# tx.net
KiCad netlist of a schematic drawn in EAGLE
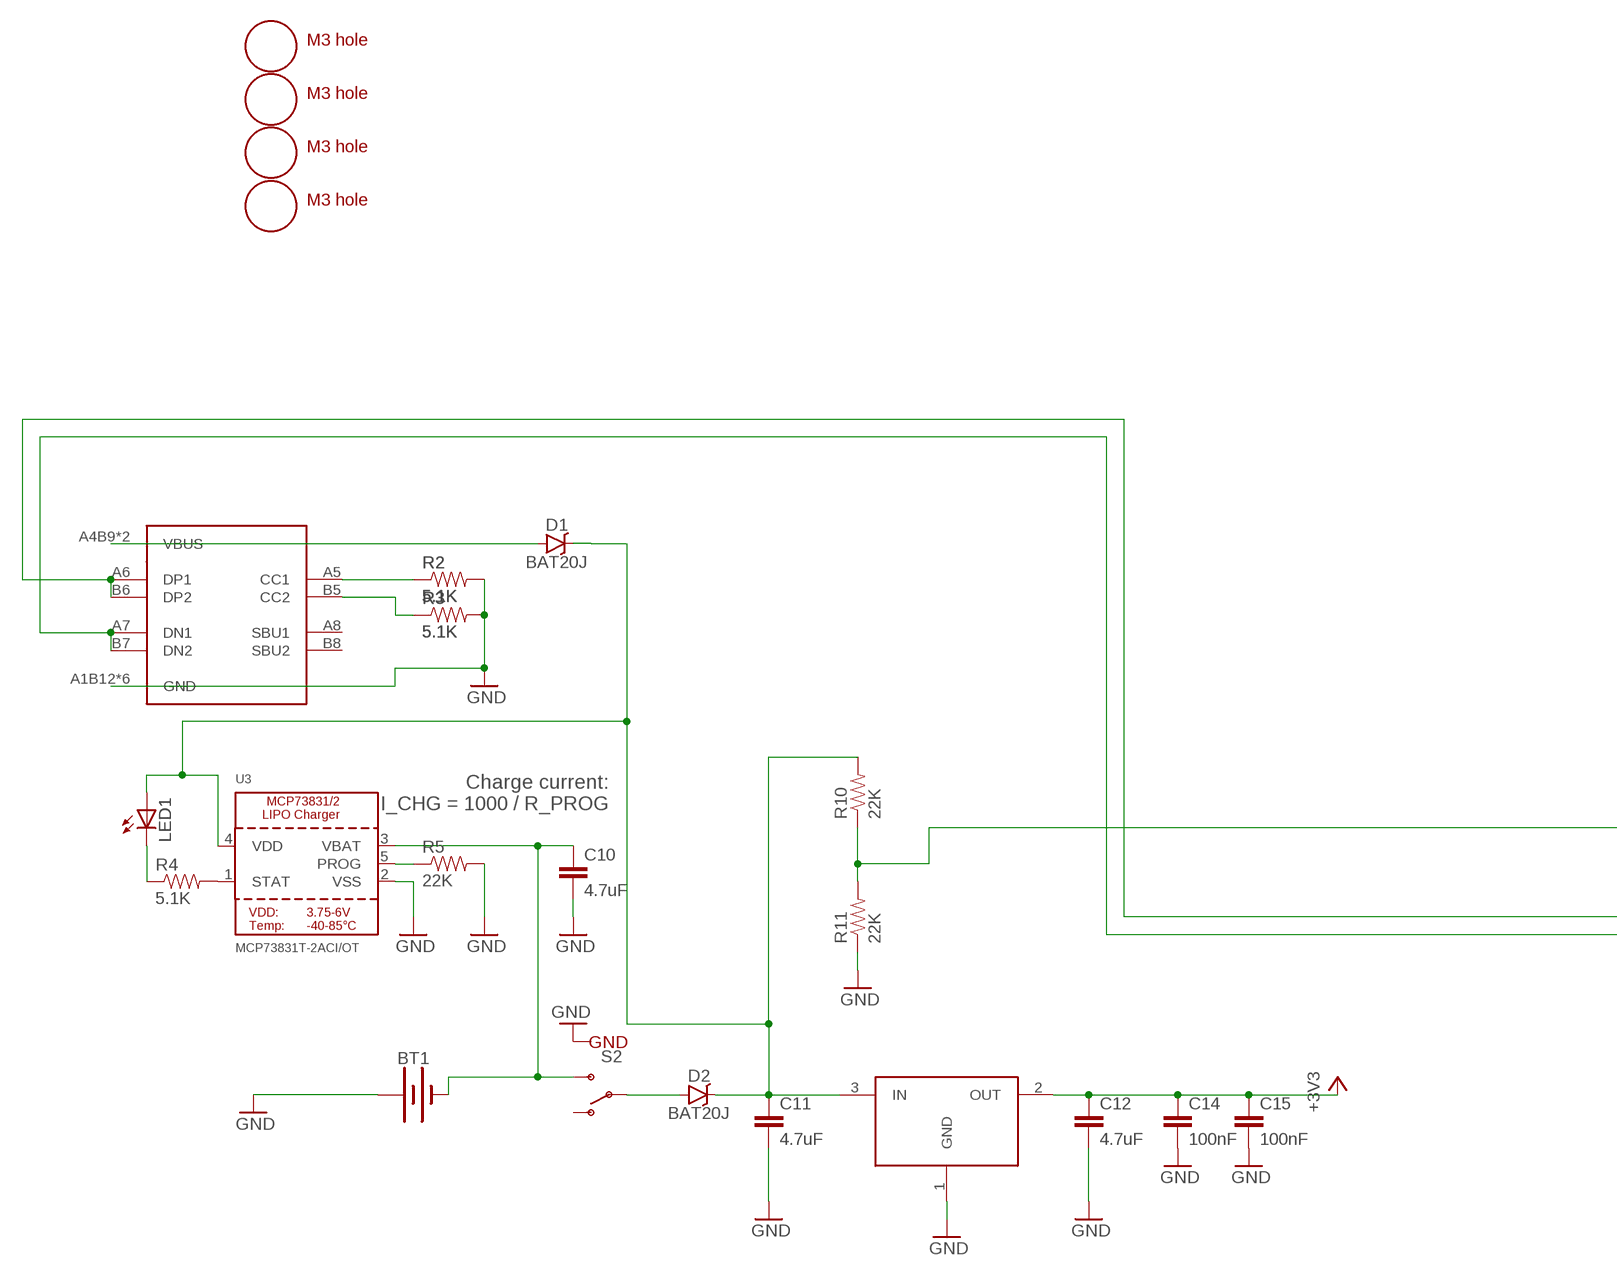
[diagram p0: schematic, sheet 1, part 1 of 2]
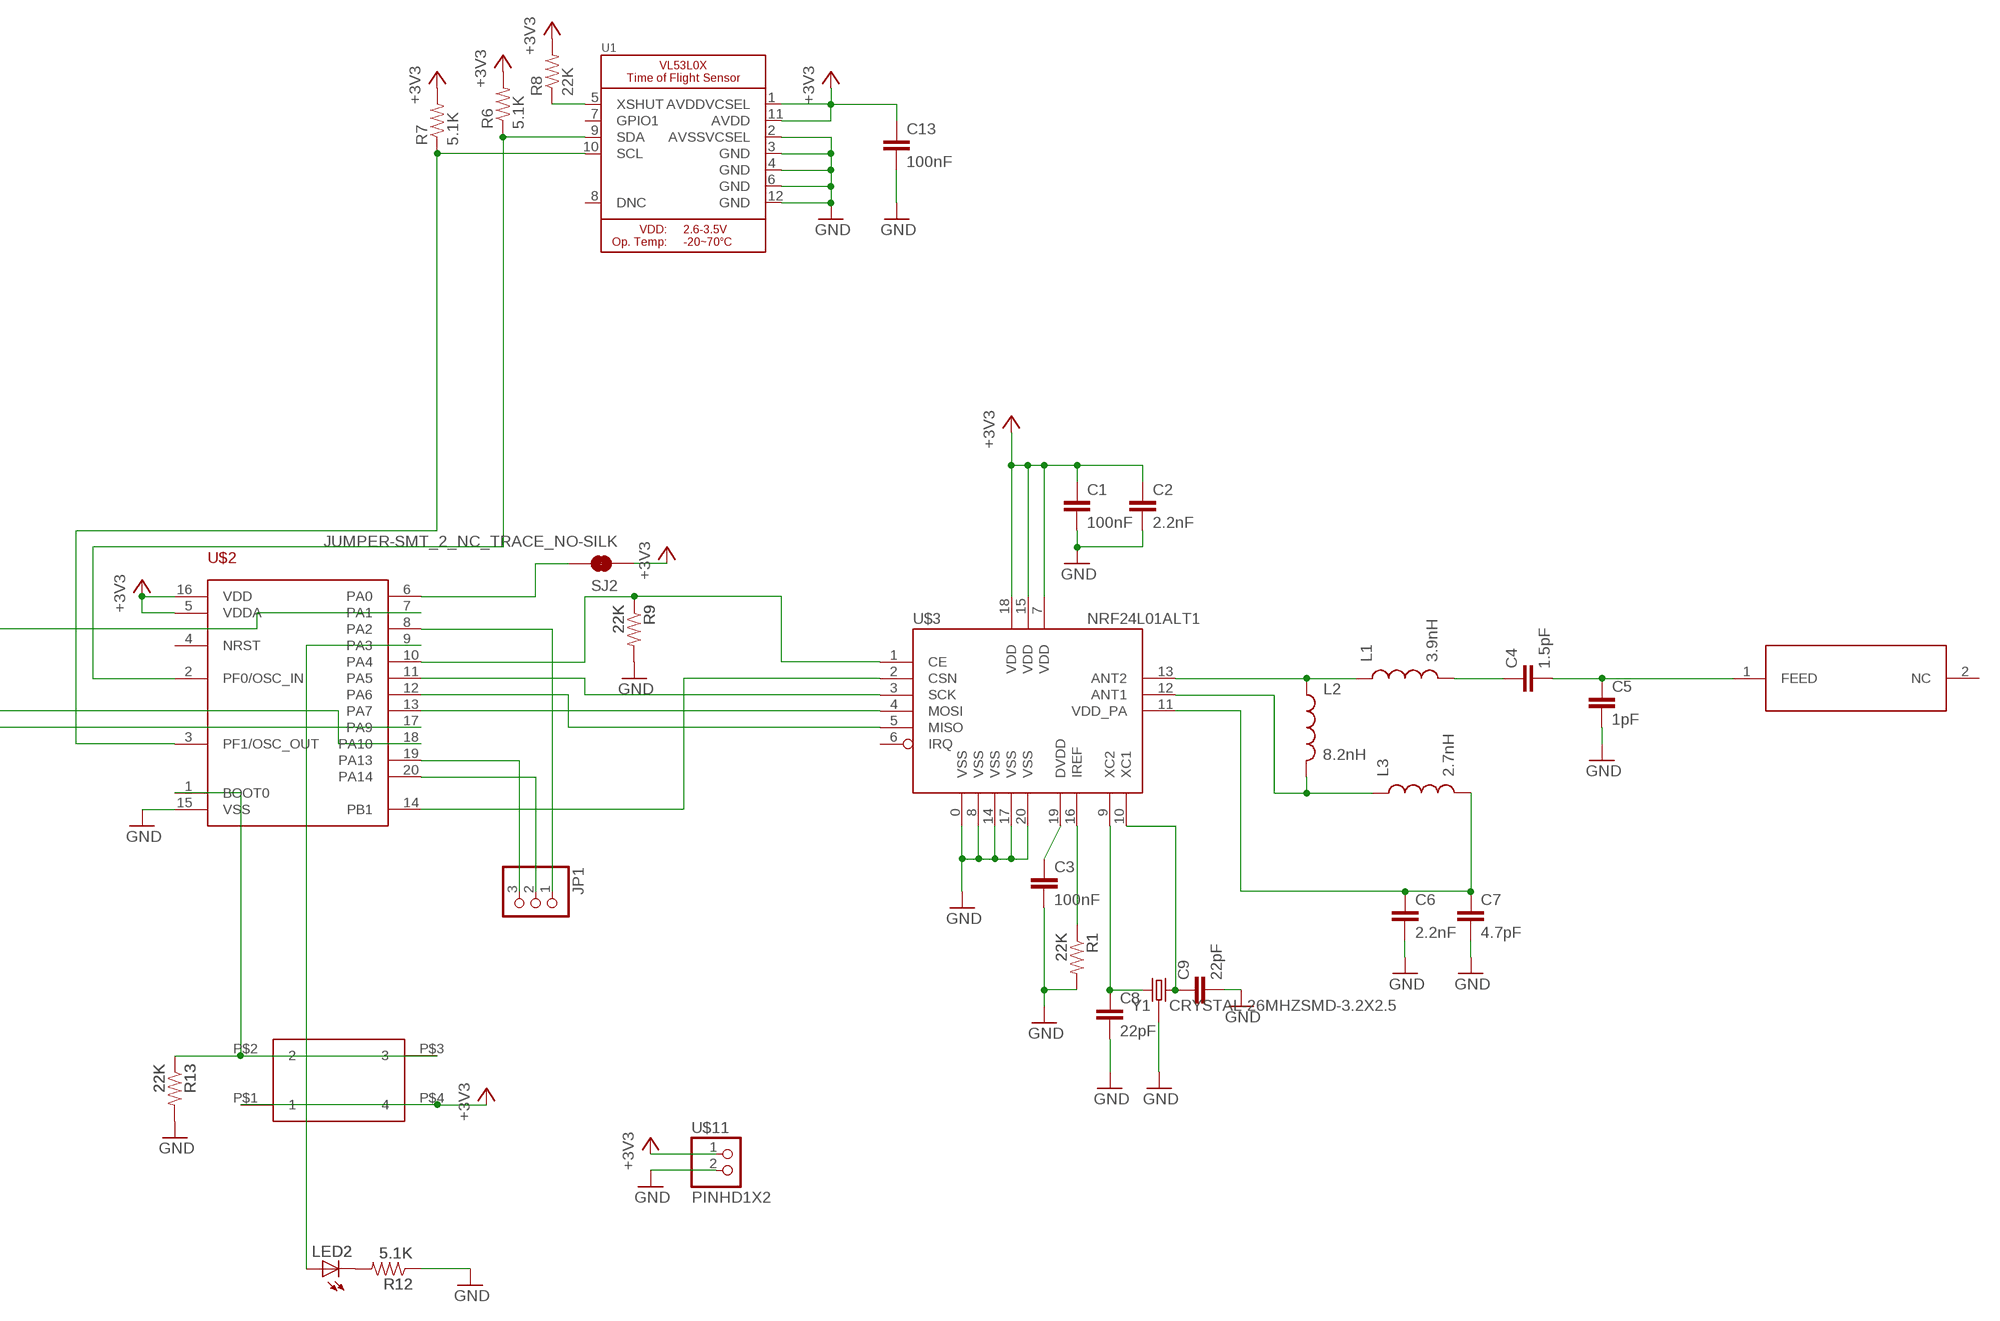
[diagram p1: schematic, sheet 1, part 2 of 2]

(export (version "E")
  (design (tool "Eeschema 10.0.6"))
  (components
    (comp (ref "BT1")
      (value "TX_SPARKFUN-BATTERIES_BATTERY-24.5MM_PTH")
      (footprint "eagle-import:TX_SPARKFUN-BATTERIES_BATTCON_24.5MM_PTH")
      (libsource (lib "eagle-import") (part "TX_SPARKFUN-BATTERIES_BATTERY-24.5MM_PTH"))
    )
    (comp (ref "C1")
      (value "100nF")
      (footprint "eagle-import:0805")
      (libsource (lib "eagle-import") (part "clock_CAP0805"))
    )
    (comp (ref "C2")
      (value "2.2nF")
      (footprint "eagle-import:0805")
      (libsource (lib "eagle-import") (part "clock_CAP0805"))
    )
    (comp (ref "C3")
      (value "100nF")
      (footprint "eagle-import:0805")
      (libsource (lib "eagle-import") (part "clock_CAP0805"))
    )
    (comp (ref "C4")
      (value "1.5pF")
      (footprint "eagle-import:0805")
      (libsource (lib "eagle-import") (part "clock_CAP0805"))
    )
    (comp (ref "C5")
      (value "1pF")
      (footprint "eagle-import:0805")
      (libsource (lib "eagle-import") (part "clock_CAP0805"))
    )
    (comp (ref "C6")
      (value "2.2nF")
      (footprint "eagle-import:0805")
      (libsource (lib "eagle-import") (part "clock_CAP0805"))
    )
    (comp (ref "C7")
      (value "4.7pF")
      (footprint "eagle-import:0805")
      (libsource (lib "eagle-import") (part "clock_CAP0805"))
    )
    (comp (ref "C8")
      (value "22pF")
      (footprint "eagle-import:0805")
      (libsource (lib "eagle-import") (part "clock_CAP0805"))
    )
    (comp (ref "C9")
      (value "22pF")
      (footprint "eagle-import:0805")
      (libsource (lib "eagle-import") (part "clock_CAP0805"))
    )
    (comp (ref "C10")
      (value "4.7uF")
      (footprint "eagle-import:0805")
      (libsource (lib "eagle-import") (part "CAP0805"))
    )
    (comp (ref "C11")
      (value "4.7uF")
      (footprint "eagle-import:0805")
      (libsource (lib "eagle-import") (part "clock_CAP0805"))
    )
    (comp (ref "C12")
      (value "4.7uF")
      (footprint "eagle-import:0805")
      (libsource (lib "eagle-import") (part "clock_CAP0805"))
    )
    (comp (ref "C13")
      (value "100nF")
      (footprint "eagle-import:0805")
      (libsource (lib "eagle-import") (part "clock_CAP0805"))
    )
    (comp (ref "C14")
      (value "100nF")
      (footprint "eagle-import:0805")
      (libsource (lib "eagle-import") (part "clock_CAP0805"))
    )
    (comp (ref "C15")
      (value "100nF")
      (footprint "eagle-import:0805")
      (libsource (lib "eagle-import") (part "clock_CAP0805"))
    )
    (comp (ref "D1")
      (value "BAT20J")
      (footprint "eagle-import:SOD-323")
      (libsource (lib "eagle-import") (part "DIODE-SCHOTTKY-BAT20J"))
    )
    (comp (ref "D2")
      (value "BAT20J")
      (footprint "eagle-import:SOD-323")
      (libsource (lib "eagle-import") (part "DIODE-SCHOTTKY-BAT20J"))
    )
    (comp (ref "JP1")
      (value "PINHD-1X3CB")
      (footprint "eagle-import:1X03-CLEANBIG")
      (libsource (lib "eagle-import") (part "PINHD-1X3CB"))
    )
    (comp (ref "L1")
      (value "3.9nH")
      (footprint "eagle-import:0805")
      (libsource (lib "eagle-import") (part "INDUCTOR0805"))
    )
    (comp (ref "L2")
      (value "8.2nH")
      (footprint "eagle-import:0805")
      (libsource (lib "eagle-import") (part "INDUCTOR0805"))
    )
    (comp (ref "L3")
      (value "2.7nH")
      (footprint "eagle-import:0805")
      (libsource (lib "eagle-import") (part "INDUCTOR0805"))
    )
    (comp (ref "LED1")
      (value "LEDCHIP-LED0805")
      (footprint "eagle-import:CHIP-LED0805")
      (libsource (lib "eagle-import") (part "LEDCHIP-LED0805"))
    )
    (comp (ref "LED2")
      (value "LEDCHIP-LED0805")
      (footprint "eagle-import:CHIP-LED0805")
      (libsource (lib "eagle-import") (part "LEDCHIP-LED0805"))
    )
    (comp (ref "R1")
      (value "22K")
      (footprint "eagle-import:0805")
      (libsource (lib "eagle-import") (part "joyAnalog_RESISTOR0805-RES"))
    )
    (comp (ref "R2")
      (value "5.1K")
      (footprint "eagle-import:0805")
      (libsource (lib "eagle-import") (part "joyAnalog_RESISTOR0805-RES"))
    )
    (comp (ref "R3")
      (value "5.1K")
      (footprint "eagle-import:0805")
      (libsource (lib "eagle-import") (part "joyAnalog_RESISTOR0805-RES"))
    )
    (comp (ref "R4")
      (value "5.1K")
      (footprint "eagle-import:0805")
      (libsource (lib "eagle-import") (part "RESISTOR0805-RES"))
    )
    (comp (ref "R5")
      (value "22K")
      (footprint "eagle-import:0805")
      (libsource (lib "eagle-import") (part "RESISTOR0805-RES"))
    )
    (comp (ref "R6")
      (value "5.1K")
      (footprint "eagle-import:0805")
      (libsource (lib "eagle-import") (part "RESISTOR0805-RES"))
    )
    (comp (ref "R7")
      (value "5.1K")
      (footprint "eagle-import:0805")
      (libsource (lib "eagle-import") (part "RESISTOR0805-RES"))
    )
    (comp (ref "R8")
      (value "22K")
      (footprint "eagle-import:0805")
      (libsource (lib "eagle-import") (part "RESISTOR0805-RES"))
    )
    (comp (ref "R9")
      (value "22K")
      (footprint "eagle-import:0805")
      (libsource (lib "eagle-import") (part "joyAnalog_RESISTOR0805-RES"))
    )
    (comp (ref "R10")
      (value "22K")
      (footprint "eagle-import:0805")
      (libsource (lib "eagle-import") (part "RESISTOR0805-RES"))
    )
    (comp (ref "R11")
      (value "22K")
      (footprint "eagle-import:0805")
      (libsource (lib "eagle-import") (part "RESISTOR0805-RES"))
    )
    (comp (ref "R12")
      (value "5.1K")
      (footprint "eagle-import:0805")
      (libsource (lib "eagle-import") (part "joyAnalog_RESISTOR0805-RES"))
    )
    (comp (ref "R13")
      (value "22K")
      (footprint "eagle-import:0805")
      (libsource (lib "eagle-import") (part "joyAnalog_RESISTOR0805-RES"))
    )
    (comp (ref "S2")
      (value "SWITCH-SPDTTDFGDFG")
      (footprint "eagle-import:SWITCH-SPST-SMD-A")
      (libsource (lib "eagle-import") (part "SWITCH-SPDTTDFGDFG"))
    )
    (comp (ref "SJ2")
      (value "JUMPER-SMT_2_NC_TRACE_NO-SILK")
      (footprint "eagle-import:SMT-JUMPER_2_NC_TRACE_NO-SILK")
      (libsource (lib "eagle-import") (part "JUMPER-SMT_2_NC_TRACE_NO-SILK"))
    )
    (comp (ref "U$1")
      (value "1206ANT_DEV")
      (footprint "eagle-import:C1206")
      (libsource (lib "eagle-import") (part "1206ANT_DEV"))
    )
    (comp (ref "U$2")
      (value "STM32F030F4")
      (footprint "eagle-import:TSSOP20")
      (libsource (lib "eagle-import") (part "STM32F030F4"))
    )
    (comp (ref "U$3")
      (value "NRF24L01ALT1")
      (footprint "eagle-import:QFN20_ALT1")
      (libsource (lib "eagle-import") (part "NRF24L01ALT1"))
    )
    (comp (ref "U$4")
      (value "USBC_16P")
      (footprint "eagle-import:USBC_16P_FOOT")
      (libsource (lib "eagle-import") (part "USBC_16P"))
    )
    (comp (ref "U$5")
      (value "M3_MOUNTING_HOLE")
      (footprint "eagle-import:M3_MOUNTING_HOLE_PACK")
      (libsource (lib "eagle-import") (part "M3_MOUNTING_HOLE"))
    )
    (comp (ref "U$6")
      (value "M3_MOUNTING_HOLE")
      (footprint "eagle-import:M3_MOUNTING_HOLE_PACK")
      (libsource (lib "eagle-import") (part "M3_MOUNTING_HOLE"))
    )
    (comp (ref "U$7")
      (value "M3_MOUNTING_HOLE")
      (footprint "eagle-import:M3_MOUNTING_HOLE_PACK")
      (libsource (lib "eagle-import") (part "M3_MOUNTING_HOLE"))
    )
    (comp (ref "U$8")
      (value "M3_MOUNTING_HOLE")
      (footprint "eagle-import:M3_MOUNTING_HOLE_PACK")
      (libsource (lib "eagle-import") (part "M3_MOUNTING_HOLE"))
    )
    (comp (ref "U$9")
      (value "XC6206_DEV")
      (footprint "eagle-import:SOT23R_INFINEON")
      (libsource (lib "eagle-import") (part "XC6206_DEV"))
    )
    (comp (ref "U$10")
      (value "324_SW324_SWITCH_FOOT_HOLE")
      (footprint "eagle-import:342_SWICH_FOOT_HOLE")
      (libsource (lib "eagle-import") (part "324_SW324_SWITCH_FOOT_HOLE"))
    )
    (comp (ref "U$11")
      (value "PINHD1X2")
      (footprint "eagle-import:1X02")
      (libsource (lib "eagle-import") (part "PINHD1X2"))
    )
    (comp (ref "U1")
      (value "VL53L0X")
      (footprint "eagle-import:LGA12_ST")
      (libsource (lib "eagle-import") (part "VL53L0X"))
    )
    (comp (ref "U3")
      (value "MCP73831T-2ACI/OT")
      (footprint "eagle-import:SOT23-5")
      (libsource (lib "eagle-import") (part "MCP73831/2"))
    )
    (comp (ref "Y1")
      (value "CRYSTAL-26MHZSMD-3.2X2.5")
      (footprint "eagle-import:CRYSTAL-SMD-3.2X2.5MM")
      (libsource (lib "eagle-import") (part "CRYSTAL-26MHZSMD-3.2X2.5"))
    )
  )
  (nets
    (net (code "1") (name "+3V3") (class "Default")
      (node (ref "C1") (pin "1") (pinfunction "1_1") (pintype "passive"))
      (node (ref "C12") (pin "1") (pinfunction "1_1") (pintype "passive"))
      (node (ref "C13") (pin "1") (pinfunction "1_1") (pintype "passive"))
      (node (ref "C14") (pin "1") (pinfunction "1_1") (pintype "passive"))
      (node (ref "C15") (pin "1") (pinfunction "1_1") (pintype "passive"))
      (node (ref "C2") (pin "1") (pinfunction "1_1") (pintype "passive"))
      (node (ref "R6") (pin "2") (pinfunction "2_2") (pintype "passive"))
      (node (ref "R7") (pin "2") (pinfunction "2_2") (pintype "passive"))
      (node (ref "R8") (pin "2") (pinfunction "2_2") (pintype "passive"))
      (node (ref "SJ2") (pin "1") (pinfunction "1_1") (pintype "passive"))
      (node (ref "U$10") (pin "P$1") (pinfunction "1_P$1") (pintype "bidirectional"))
      (node (ref "U$10") (pin "P$4") (pinfunction "4_P$4") (pintype "bidirectional"))
      (node (ref "U$11") (pin "1") (pinfunction "1_1") (pintype "passive"))
      (node (ref "U$2") (pin "16") (pinfunction "VDD_16") (pintype "bidirectional"))
      (node (ref "U$2") (pin "5") (pinfunction "VDDA_5") (pintype "bidirectional"))
      (node (ref "U$3") (pin "15") (pinfunction "VDD_15") (pintype "power_in"))
      (node (ref "U$3") (pin "18") (pinfunction "VDD_18") (pintype "power_in"))
      (node (ref "U$3") (pin "7") (pinfunction "VDD_7") (pintype "power_in"))
      (node (ref "U$9") (pin "2") (pinfunction "OUT_2") (pintype "bidirectional"))
      (node (ref "U1") (pin "1") (pinfunction "AVDDVCSEL_1") (pintype "power_in"))
      (node (ref "U1") (pin "11") (pinfunction "AVDD_11") (pintype "power_in"))
    )
    (net (code "2") (name "GND") (class "Default")
      (node (ref "BT1") (pin "2") (pinfunction "+_2") (pintype "power_in"))
      (node (ref "C1") (pin "2") (pinfunction "2_2") (pintype "passive"))
      (node (ref "C10") (pin "2") (pinfunction "2_2") (pintype "passive"))
      (node (ref "C11") (pin "2") (pinfunction "2_2") (pintype "passive"))
      (node (ref "C12") (pin "2") (pinfunction "2_2") (pintype "passive"))
      (node (ref "C13") (pin "2") (pinfunction "2_2") (pintype "passive"))
      (node (ref "C14") (pin "2") (pinfunction "2_2") (pintype "passive"))
      (node (ref "C15") (pin "2") (pinfunction "2_2") (pintype "passive"))
      (node (ref "C2") (pin "2") (pinfunction "2_2") (pintype "passive"))
      (node (ref "C3") (pin "2") (pinfunction "2_2") (pintype "passive"))
      (node (ref "C5") (pin "2") (pinfunction "2_2") (pintype "passive"))
      (node (ref "C6") (pin "2") (pinfunction "2_2") (pintype "passive"))
      (node (ref "C7") (pin "2") (pinfunction "2_2") (pintype "passive"))
      (node (ref "C8") (pin "2") (pinfunction "2_2") (pintype "passive"))
      (node (ref "C9") (pin "2") (pinfunction "2_2") (pintype "passive"))
      (node (ref "R1") (pin "2") (pinfunction "2_2") (pintype "passive"))
      (node (ref "R11") (pin "1") (pinfunction "1_1") (pintype "passive"))
      (node (ref "R12") (pin "1") (pinfunction "1_1") (pintype "passive"))
      (node (ref "R13") (pin "2") (pinfunction "2_2") (pintype "passive"))
      (node (ref "R2") (pin "2") (pinfunction "2_2") (pintype "passive"))
      (node (ref "R3") (pin "2") (pinfunction "2_2") (pintype "passive"))
      (node (ref "R5") (pin "2") (pinfunction "2_2") (pintype "passive"))
      (node (ref "R9") (pin "2") (pinfunction "2_2") (pintype "passive"))
      (node (ref "S2") (pin "G1") (pinfunction "GND_G1") (pintype "passive"))
      (node (ref "S2") (pin "G2") (pinfunction "GND_G2") (pintype "passive"))
      (node (ref "S2") (pin "G3") (pinfunction "GND_G3") (pintype "passive"))
      (node (ref "S2") (pin "G4") (pinfunction "GND_G4") (pintype "passive"))
      (node (ref "U$11") (pin "2") (pinfunction "2_2") (pintype "passive"))
      (node (ref "U$2") (pin "15") (pinfunction "VSS_15") (pintype "bidirectional"))
      (node (ref "U$3") (pin "0") (pinfunction "VSS_0") (pintype "power_in"))
      (node (ref "U$3") (pin "14") (pinfunction "VSS_14") (pintype "power_in"))
      (node (ref "U$3") (pin "17") (pinfunction "VSS_17") (pintype "power_in"))
      (node (ref "U$3") (pin "20") (pinfunction "VSS_20") (pintype "power_in"))
      (node (ref "U$3") (pin "8") (pinfunction "VSS_8") (pintype "power_in"))
      (node (ref "U$4") (pin "A1B12") (pinfunction "GND_A1B12") (pintype "bidirectional"))
      (node (ref "U$4") (pin "B11A12") (pinfunction "GND_B11A12") (pintype "bidirectional"))
      (node (ref "U$4") (pin "P$13") (pinfunction "GND_P$13") (pintype "bidirectional"))
      (node (ref "U$4") (pin "P$14") (pinfunction "GND_P$14") (pintype "bidirectional"))
      (node (ref "U$4") (pin "P$15") (pinfunction "GND_P$15") (pintype "bidirectional"))
      (node (ref "U$4") (pin "P$16") (pinfunction "GND_P$16") (pintype "bidirectional"))
      (node (ref "U$9") (pin "1") (pinfunction "GND_1") (pintype "bidirectional"))
      (node (ref "U1") (pin "12") (pinfunction "GND_12") (pintype "power_in"))
      (node (ref "U1") (pin "2") (pinfunction "AVSSVCSEL_2") (pintype "power_in"))
      (node (ref "U1") (pin "3") (pinfunction "GND_3") (pintype "power_in"))
      (node (ref "U1") (pin "4") (pinfunction "GND_4") (pintype "power_in"))
      (node (ref "U1") (pin "6") (pinfunction "GND_6") (pintype "power_in"))
      (node (ref "U3") (pin "2") (pinfunction "VSS_2") (pintype "power_in"))
      (node (ref "Y1") (pin "2") (pinfunction "3_2") (pintype "passive"))
      (node (ref "Y1") (pin "4") (pinfunction "3_4") (pintype "passive"))
    )
    (net (code "3") (name "Net-(BT1--)") (class "Default")
      (node (ref "BT1") (pin "1") (pinfunction "-_1") (pintype "power_in"))
      (node (ref "C10") (pin "1") (pinfunction "1_1") (pintype "passive"))
      (node (ref "S2") (pin "3") (pinfunction "S_3") (pintype "passive"))
      (node (ref "U3") (pin "3") (pinfunction "VBAT_3") (pintype "power_in"))
    )
    (net (code "4") (name "Net-(C4-Pad1)") (class "Default")
      (node (ref "C4") (pin "1") (pinfunction "1_1") (pintype "passive"))
      (node (ref "L1") (pin "2") (pinfunction "2_2") (pintype "passive"))
    )
    (net (code "5") (name "Net-(D1-PadA)") (class "Default")
      (node (ref "D1") (pin "A") (pinfunction "A_A") (pintype "passive"))
      (node (ref "U$4") (pin "A4B9") (pinfunction "VBUS_A4B9") (pintype "bidirectional"))
      (node (ref "U$4") (pin "B4A9") (pinfunction "VBUS_B4A9") (pintype "bidirectional"))
    )
    (net (code "6") (name "Net-(LED1-PadC)") (class "Default")
      (node (ref "LED1") (pin "C") (pinfunction "C_C") (pintype "passive"))
      (node (ref "R4") (pin "1") (pinfunction "1_1") (pintype "passive"))
    )
    (net (code "7") (name "Net-(LED2-PadC)") (class "Default")
      (node (ref "LED2") (pin "C") (pinfunction "C_C") (pintype "passive"))
      (node (ref "R12") (pin "2") (pinfunction "2_2") (pintype "passive"))
    )
    (net (code "8") (name "Net-(S2-P)") (class "Default")
      (node (ref "D2") (pin "A") (pinfunction "A_A") (pintype "passive"))
      (node (ref "S2") (pin "2") (pinfunction "P_2") (pintype "passive"))
    )
    (net (code "9") (name "Net-(U$1-FEED)") (class "Default")
      (node (ref "C4") (pin "2") (pinfunction "2_2") (pintype "passive"))
      (node (ref "C5") (pin "1") (pinfunction "1_1") (pintype "passive"))
      (node (ref "U$1") (pin "1") (pinfunction "FEED_1") (pintype "bidirectional"))
    )
    (net (code "10") (name "Net-(U$2-PA0)") (class "Default")
      (node (ref "SJ2") (pin "2") (pinfunction "2_2") (pintype "passive"))
      (node (ref "U$2") (pin "6") (pinfunction "PA0_6") (pintype "bidirectional"))
    )
    (net (code "11") (name "Net-(U$2-PA1)") (class "Default")
      (node (ref "R10") (pin "1") (pinfunction "1_1") (pintype "passive"))
      (node (ref "R11") (pin "2") (pinfunction "2_2") (pintype "passive"))
      (node (ref "U$2") (pin "7") (pinfunction "PA1_7") (pintype "bidirectional"))
    )
    (net (code "12") (name "Net-(U$2-PA2)") (class "Default")
      (node (ref "JP1") (pin "1") (pinfunction "1_1") (pintype "passive"))
      (node (ref "U$2") (pin "8") (pinfunction "PA2_8") (pintype "bidirectional"))
    )
    (net (code "13") (name "Net-(U$2-PA3)") (class "Default")
      (node (ref "LED2") (pin "A") (pinfunction "A_A") (pintype "passive"))
      (node (ref "U$2") (pin "9") (pinfunction "PA3_9") (pintype "bidirectional"))
    )
    (net (code "14") (name "Net-(U$2-PA4)") (class "Default")
      (node (ref "R9") (pin "1") (pinfunction "1_1") (pintype "passive"))
      (node (ref "U$2") (pin "10") (pinfunction "PA4_10") (pintype "bidirectional"))
      (node (ref "U$3") (pin "1") (pinfunction "CE_1") (pintype "input"))
    )
    (net (code "15") (name "Net-(U$2-PA5)") (class "Default")
      (node (ref "U$2") (pin "11") (pinfunction "PA5_11") (pintype "bidirectional"))
      (node (ref "U$3") (pin "3") (pinfunction "SCK_3") (pintype "input"))
    )
    (net (code "16") (name "Net-(U$2-PA6)") (class "Default")
      (node (ref "U$2") (pin "12") (pinfunction "PA6_12") (pintype "bidirectional"))
      (node (ref "U$3") (pin "5") (pinfunction "MISO_5") (pintype "output"))
    )
    (net (code "17") (name "Net-(U$2-PA7)") (class "Default")
      (node (ref "U$2") (pin "13") (pinfunction "PA7_13") (pintype "bidirectional"))
      (node (ref "U$3") (pin "4") (pinfunction "MOSI_4") (pintype "input"))
    )
    (net (code "18") (name "Net-(U$2-PA9)") (class "Default")
      (node (ref "U$2") (pin "17") (pinfunction "PA9_17") (pintype "bidirectional"))
      (node (ref "U$4") (pin "A7") (pinfunction "DN1_A7") (pintype "bidirectional"))
      (node (ref "U$4") (pin "B7") (pinfunction "DN2_B7") (pintype "bidirectional"))
    )
    (net (code "19") (name "Net-(U$2-PA10)") (class "Default")
      (node (ref "U$2") (pin "18") (pinfunction "PA10_18") (pintype "bidirectional"))
      (node (ref "U$4") (pin "A6") (pinfunction "DP1_A6") (pintype "bidirectional"))
      (node (ref "U$4") (pin "B6") (pinfunction "DP2_B6") (pintype "bidirectional"))
    )
    (net (code "20") (name "Net-(U$2-PA13)") (class "Default")
      (node (ref "JP1") (pin "3") (pinfunction "3_3") (pintype "passive"))
      (node (ref "U$2") (pin "19") (pinfunction "PA13_19") (pintype "bidirectional"))
    )
    (net (code "21") (name "Net-(U$2-PA14)") (class "Default")
      (node (ref "JP1") (pin "2") (pinfunction "2_2") (pintype "passive"))
      (node (ref "U$2") (pin "20") (pinfunction "PA14_20") (pintype "bidirectional"))
    )
    (net (code "22") (name "Net-(U$2-PB1)") (class "Default")
      (node (ref "U$2") (pin "14") (pinfunction "PB1_14") (pintype "bidirectional"))
      (node (ref "U$3") (pin "2") (pinfunction "CSN_2") (pintype "input"))
    )
    (net (code "23") (name "Net-(U$2-PF0{slash}OSC_IN)") (class "Default")
      (node (ref "R6") (pin "1") (pinfunction "1_1") (pintype "passive"))
      (node (ref "U$2") (pin "2") (pinfunction "PF0/OSC_IN_2") (pintype "bidirectional"))
      (node (ref "U1") (pin "9") (pinfunction "SDA_9") (pintype "open_collector"))
    )
    (net (code "24") (name "Net-(U$2-PF1{slash}OSC_OUT)") (class "Default")
      (node (ref "R7") (pin "1") (pinfunction "1_1") (pintype "passive"))
      (node (ref "U$2") (pin "3") (pinfunction "PF1/OSC_OUT_3") (pintype "bidirectional"))
      (node (ref "U1") (pin "10") (pinfunction "SCL_10") (pintype "open_collector"))
    )
    (net (code "25") (name "Net-(U$3-ANT1)") (class "Default")
      (node (ref "L2") (pin "2") (pinfunction "2_2") (pintype "passive"))
      (node (ref "L3") (pin "1") (pinfunction "1_1") (pintype "passive"))
      (node (ref "U$3") (pin "12") (pinfunction "ANT1_12") (pintype "output"))
    )
    (net (code "26") (name "Net-(U$3-ANT2)") (class "Default")
      (node (ref "L1") (pin "1") (pinfunction "1_1") (pintype "passive"))
      (node (ref "L2") (pin "1") (pinfunction "1_1") (pintype "passive"))
      (node (ref "U$3") (pin "13") (pinfunction "ANT2_13") (pintype "output"))
    )
    (net (code "27") (name "Net-(U$3-DVDD)") (class "Default")
      (node (ref "C3") (pin "1") (pinfunction "1_1") (pintype "passive"))
      (node (ref "U$3") (pin "19") (pinfunction "DVDD_19") (pintype "power_in"))
    )
    (net (code "28") (name "Net-(U$3-IREF)") (class "Default")
      (node (ref "R1") (pin "1") (pinfunction "1_1") (pintype "passive"))
      (node (ref "U$3") (pin "16") (pinfunction "IREF_16") (pintype "input"))
    )
    (net (code "29") (name "Net-(U$3-VDD_PA)") (class "Default")
      (node (ref "C6") (pin "1") (pinfunction "1_1") (pintype "passive"))
      (node (ref "C7") (pin "1") (pinfunction "1_1") (pintype "passive"))
      (node (ref "L3") (pin "2") (pinfunction "2_2") (pintype "passive"))
      (node (ref "U$3") (pin "11") (pinfunction "VDD_PA_11") (pintype "power_in"))
    )
    (net (code "30") (name "Net-(U$3-XC1)") (class "Default")
      (node (ref "C9") (pin "1") (pinfunction "1_1") (pintype "passive"))
      (node (ref "U$3") (pin "10") (pinfunction "XC1_10") (pintype "input"))
      (node (ref "Y1") (pin "3") (pinfunction "2_3") (pintype "passive"))
    )
    (net (code "31") (name "Net-(U$3-XC2)") (class "Default")
      (node (ref "C8") (pin "1") (pinfunction "1_1") (pintype "passive"))
      (node (ref "U$3") (pin "9") (pinfunction "XC2_9") (pintype "input"))
      (node (ref "Y1") (pin "1") (pinfunction "1_1") (pintype "passive"))
    )
    (net (code "32") (name "Net-(U$4-CC1)") (class "Default")
      (node (ref "R2") (pin "1") (pinfunction "1_1") (pintype "passive"))
      (node (ref "U$4") (pin "A5") (pinfunction "CC1_A5") (pintype "bidirectional"))
    )
    (net (code "33") (name "Net-(U$4-CC2)") (class "Default")
      (node (ref "R3") (pin "1") (pinfunction "1_1") (pintype "passive"))
      (node (ref "U$4") (pin "B5") (pinfunction "CC2_B5") (pintype "bidirectional"))
    )
    (net (code "34") (name "Net-(U$9-IN)") (class "Default")
      (node (ref "C11") (pin "1") (pinfunction "1_1") (pintype "passive"))
      (node (ref "D1") (pin "C") (pinfunction "C_C") (pintype "passive"))
      (node (ref "D2") (pin "C") (pinfunction "C_C") (pintype "passive"))
      (node (ref "LED1") (pin "A") (pinfunction "A_A") (pintype "passive"))
      (node (ref "R10") (pin "2") (pinfunction "2_2") (pintype "passive"))
      (node (ref "U$9") (pin "3") (pinfunction "IN_3") (pintype "bidirectional"))
      (node (ref "U3") (pin "4") (pinfunction "VDD_4") (pintype "power_in"))
    )
    (net (code "35") (name "Net-(U$10-2)") (class "Default")
      (node (ref "R13") (pin "1") (pinfunction "1_1") (pintype "passive"))
      (node (ref "U$10") (pin "P$2") (pinfunction "2_P$2") (pintype "bidirectional"))
      (node (ref "U$10") (pin "P$3") (pinfunction "3_P$3") (pintype "bidirectional"))
      (node (ref "U$2") (pin "1") (pinfunction "BOOT0_1") (pintype "bidirectional"))
    )
    (net (code "36") (name "Net-(U1-XSHUT)") (class "Default")
      (node (ref "R8") (pin "1") (pinfunction "1_1") (pintype "passive"))
      (node (ref "U1") (pin "5") (pinfunction "XSHUT_5") (pintype "input"))
    )
    (net (code "37") (name "Net-(U3-PROG)") (class "Default")
      (node (ref "R5") (pin "1") (pinfunction "1_1") (pintype "passive"))
      (node (ref "U3") (pin "5") (pinfunction "PROG_5") (pintype "input"))
    )
    (net (code "38") (name "Net-(U3-STAT)") (class "Default")
      (node (ref "R4") (pin "2") (pinfunction "2_2") (pintype "passive"))
      (node (ref "U3") (pin "1") (pinfunction "STAT_1") (pintype "output"))
    )
    (net (code "39") (name "unconnected-(S2-O-Pad1)") (class "Default")
      (node (ref "S2") (pin "1") (pinfunction "O_1") (pintype "passive"))
    )
    (net (code "40") (name "unconnected-(U$1-NC-Pad2)") (class "Default")
      (node (ref "U$1") (pin "2") (pinfunction "NC_2") (pintype "bidirectional"))
    )
    (net (code "41") (name "unconnected-(U$2-NRST-Pad4)") (class "Default")
      (node (ref "U$2") (pin "4") (pinfunction "NRST_4") (pintype "bidirectional"))
    )
    (net (code "42") (name "unconnected-(U$3-IRQ-Pad6)") (class "Default")
      (node (ref "U$3") (pin "6") (pinfunction "IRQ_6") (pintype "output"))
    )
    (net (code "43") (name "unconnected-(U$4-SBU1-PadA8)") (class "Default")
      (node (ref "U$4") (pin "A8") (pinfunction "SBU1_A8") (pintype "bidirectional"))
    )
    (net (code "44") (name "unconnected-(U$4-SBU2-PadB8)") (class "Default")
      (node (ref "U$4") (pin "B8") (pinfunction "SBU2_B8") (pintype "bidirectional"))
    )
    (net (code "45") (name "unconnected-(U1-DNC-Pad8)") (class "Default")
      (node (ref "U1") (pin "8") (pinfunction "DNC_8") (pintype "no_connect"))
    )
    (net (code "46") (name "unconnected-(U1-GPIO1-Pad7)") (class "Default")
      (node (ref "U1") (pin "7") (pinfunction "GPIO1_7") (pintype "output"))
    )
  )
)
